# IO_Expander.net
KiCad netlist of a schematic drawn in Altium Designer
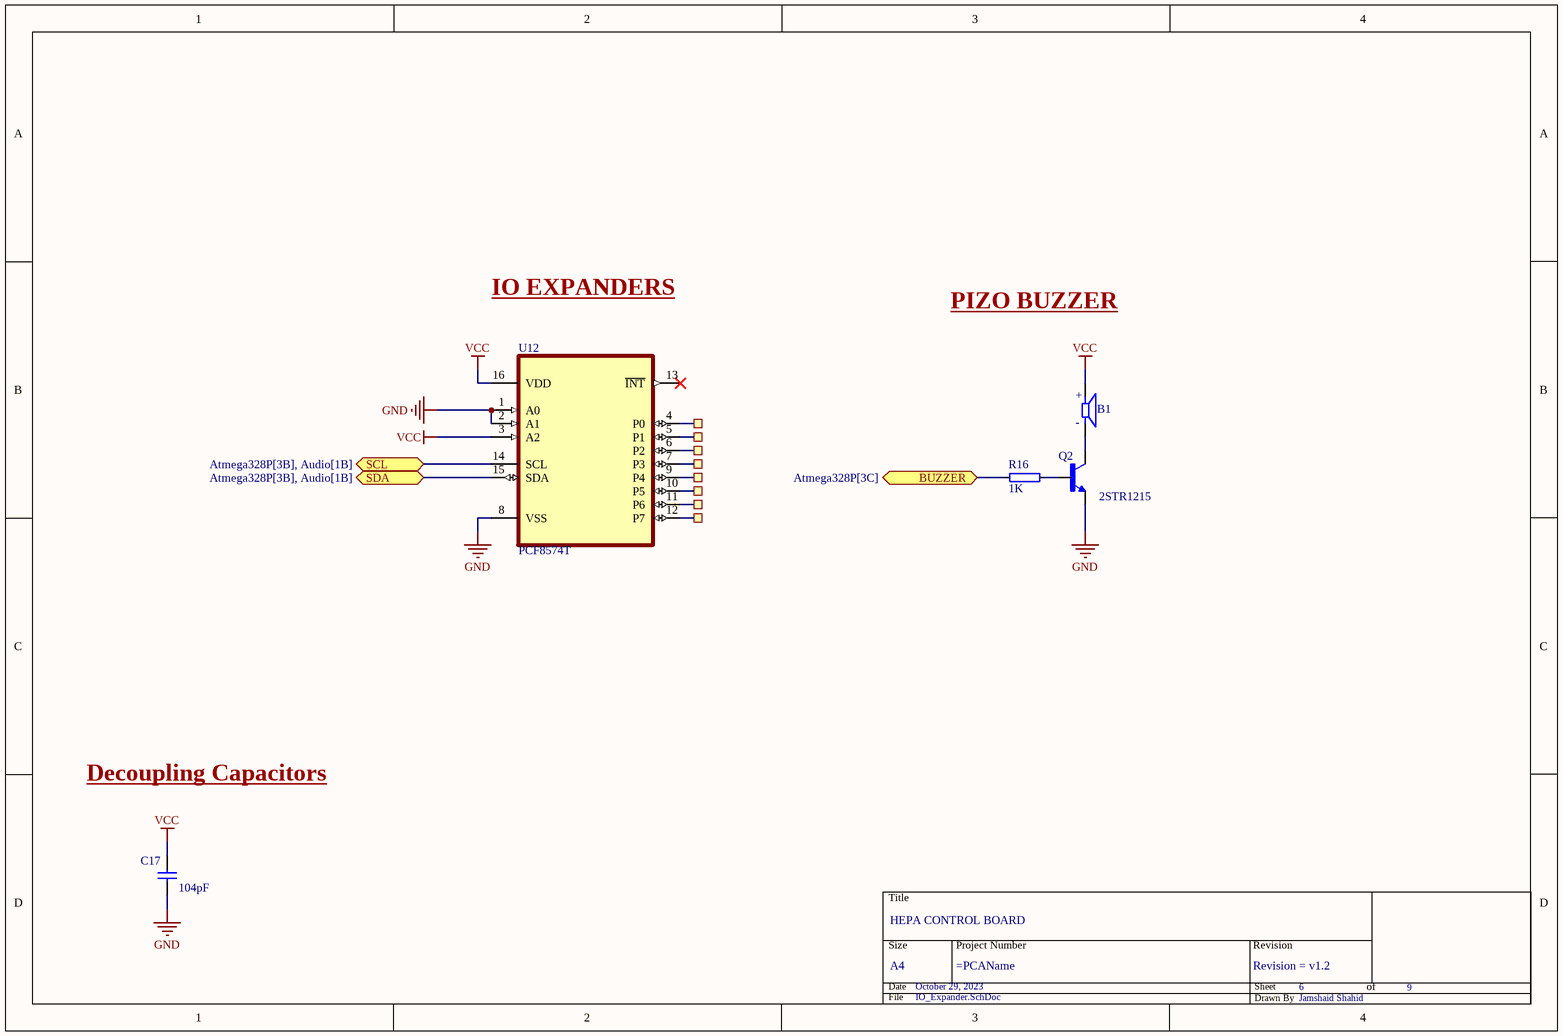
[diagram p0: IO_Expander.SchDoc]

(export (version "E")
  (design (tool "Eeschema 10.0.6"))
  (components
    (comp (ref "B1")
      (value "CST-951AP")
      (footprint "CUI_CST-951AP")
      (description "9 mm, 5 V, 85 dB, Through Hole, Magnetic Audio Transducer B")
      (fields (field (name "PUBLISHER") "Metal Circuits"))
      (libsource (lib "HEPA_LIB") (part "CST-951AP"))
    )
    (comp (ref "C17")
      (value "104pF")
      (footprint "CAPC2012X140N")
      (fields (field (name "PART NUMBER") "CAP_0805") (field (name "PUBLISHER") "Metal Circuits"))
      (libsource (lib "HEPA_LIB") (part "CAP_0805"))
    )
    (comp (ref "Q2")
      (value "2STR1215")
      (footprint "SOT95P280X125-3N")
      (description "Bipolar (BJT) Transistor NPN 15 V 1.5 A - 500 mW Surface Mount SOT-23-3")
      (fields (field (name "MANUFACTURER") "ST") (field (name "PUBLISHER") "Metal Circuits"))
      (libsource (lib "HEPA_LIB") (part "2STR1215"))
    )
    (comp (ref "R16")
      (value "1K")
      (footprint "RESC2012X65N")
      (description "RES SMD 1% 1/10W 0805")
      (fields (field (name "PART NUMBER") "RES_0805") (field (name "PUBLISHER") "Metal Circuits"))
      (libsource (lib "HEPA_LIB") (part "RES_0805"))
    )
    (comp (ref "TP3")
      (value "TP")
      (footprint "TESTPAD-TH")
      (description "Testpoint, through hole")
      (fields (field (name "PART NUMBER") "Testpoint TH") (field (name "PUBLISHER") "Nordic Semiconductor"))
      (libsource (lib "HEPA_LIB") (part "TESTPAD_TH"))
    )
    (comp (ref "TP4")
      (value "TP")
      (footprint "TESTPAD-TH")
      (description "Testpoint, through hole")
      (fields (field (name "PART NUMBER") "Testpoint TH") (field (name "PUBLISHER") "Nordic Semiconductor"))
      (libsource (lib "HEPA_LIB") (part "TESTPAD_TH"))
    )
    (comp (ref "TP5")
      (value "TP")
      (footprint "TESTPAD-TH")
      (description "Testpoint, through hole")
      (fields (field (name "PART NUMBER") "Testpoint TH") (field (name "PUBLISHER") "Nordic Semiconductor"))
      (libsource (lib "HEPA_LIB") (part "TESTPAD_TH"))
    )
    (comp (ref "TP6")
      (value "TP")
      (footprint "TESTPAD-TH")
      (description "Testpoint, through hole")
      (fields (field (name "PART NUMBER") "Testpoint TH") (field (name "PUBLISHER") "Nordic Semiconductor"))
      (libsource (lib "HEPA_LIB") (part "TESTPAD_TH"))
    )
    (comp (ref "TP7")
      (value "TP")
      (footprint "TESTPAD-TH")
      (description "Testpoint, through hole")
      (fields (field (name "PART NUMBER") "Testpoint TH") (field (name "PUBLISHER") "Nordic Semiconductor"))
      (libsource (lib "HEPA_LIB") (part "TESTPAD_TH"))
    )
    (comp (ref "TP8")
      (value "TP")
      (footprint "TESTPAD-TH")
      (description "Testpoint, through hole")
      (fields (field (name "PART NUMBER") "Testpoint TH") (field (name "PUBLISHER") "Nordic Semiconductor"))
      (libsource (lib "HEPA_LIB") (part "TESTPAD_TH"))
    )
    (comp (ref "TP9")
      (value "TP")
      (footprint "TESTPAD-TH")
      (description "Testpoint, through hole")
      (fields (field (name "PART NUMBER") "Testpoint TH") (field (name "PUBLISHER") "Nordic Semiconductor"))
      (libsource (lib "HEPA_LIB") (part "TESTPAD_TH"))
    )
    (comp (ref "TP10")
      (value "TP")
      (footprint "TESTPAD-TH")
      (description "Testpoint, through hole")
      (fields (field (name "PART NUMBER") "Testpoint TH") (field (name "PUBLISHER") "Nordic Semiconductor"))
      (libsource (lib "HEPA_LIB") (part "TESTPAD_TH"))
    )
    (comp (ref "U12")
      (value "PCF8574T")
      (footprint "SOIC127P1032X265-16N")
      (description "IC XPNDR 100KHZ I2C 16SO")
      (fields
        (field (name "PART NUMBER") "PCF8574T/3,518")
        (field (name "MANUFACTURER") "NXP")
        (field (name "PUBLISHER") "Metal Circuits")
      )
      (libsource (lib "HEPA_LIB") (part "PCF8574T/3,518"))
    )
  )
  (nets
    (net (code "1") (name "/BUZZER") (class "Default")
      (node (ref "R16") (pin "2") (pinfunction "2_2") (pintype "passive"))
    )
    (net (code "2") (name "/SCL") (class "Default")
      (node (ref "U12") (pin "14") (pinfunction "SCL_14") (pintype "passive"))
    )
    (net (code "3") (name "/SDA") (class "Default")
      (node (ref "U12") (pin "15") (pinfunction "SDA_15") (pintype "bidirectional"))
    )
    (net (code "4") (name "GND") (class "Default")
      (node (ref "C17") (pin "1") (pinfunction "1_1") (pintype "passive"))
      (node (ref "Q2") (pin "2") (pinfunction "E_2") (pintype "passive"))
      (node (ref "U12") (pin "1") (pinfunction "A0_1") (pintype "input"))
      (node (ref "U12") (pin "2") (pinfunction "A1_2") (pintype "input"))
      (node (ref "U12") (pin "8") (pinfunction "VSS_8") (pintype "passive"))
    )
    (net (code "5") (name "Net-(Q2-B)") (class "Default")
      (node (ref "Q2") (pin "1") (pinfunction "B_1") (pintype "passive"))
      (node (ref "R16") (pin "1") (pinfunction "1_1") (pintype "passive"))
    )
    (net (code "6") (name "Net-(Q2-C)") (class "Default")
      (node (ref "B1") (pin "M") (pinfunction "M_M") (pintype "passive"))
      (node (ref "Q2") (pin "3") (pinfunction "C_3") (pintype "passive"))
    )
    (net (code "7") (name "Net-(U12-P0)") (class "Default")
      (node (ref "TP3") (pin "1") (pinfunction "1_1") (pintype "passive"))
      (node (ref "U12") (pin "4") (pinfunction "P0_4") (pintype "bidirectional"))
    )
    (net (code "8") (name "Net-(U12-P1)") (class "Default")
      (node (ref "TP4") (pin "1") (pinfunction "1_1") (pintype "passive"))
      (node (ref "U12") (pin "5") (pinfunction "P1_5") (pintype "bidirectional"))
    )
    (net (code "9") (name "Net-(U12-P2)") (class "Default")
      (node (ref "TP5") (pin "1") (pinfunction "1_1") (pintype "passive"))
      (node (ref "U12") (pin "6") (pinfunction "P2_6") (pintype "bidirectional"))
    )
    (net (code "10") (name "Net-(U12-P3)") (class "Default")
      (node (ref "TP6") (pin "1") (pinfunction "1_1") (pintype "passive"))
      (node (ref "U12") (pin "7") (pinfunction "P3_7") (pintype "bidirectional"))
    )
    (net (code "11") (name "Net-(U12-P4)") (class "Default")
      (node (ref "TP7") (pin "1") (pinfunction "1_1") (pintype "passive"))
      (node (ref "U12") (pin "9") (pinfunction "P4_9") (pintype "bidirectional"))
    )
    (net (code "12") (name "Net-(U12-P5)") (class "Default")
      (node (ref "TP8") (pin "1") (pinfunction "1_1") (pintype "passive"))
      (node (ref "U12") (pin "10") (pinfunction "P5_10") (pintype "bidirectional"))
    )
    (net (code "13") (name "Net-(U12-P6)") (class "Default")
      (node (ref "TP9") (pin "1") (pinfunction "1_1") (pintype "passive"))
      (node (ref "U12") (pin "11") (pinfunction "P6_11") (pintype "bidirectional"))
    )
    (net (code "14") (name "Net-(U12-P7)") (class "Default")
      (node (ref "TP10") (pin "1") (pinfunction "1_1") (pintype "passive"))
      (node (ref "U12") (pin "12") (pinfunction "P7_12") (pintype "bidirectional"))
    )
    (net (code "15") (name "VCC") (class "Default")
      (node (ref "B1") (pin "P") (pinfunction "P_P") (pintype "passive"))
      (node (ref "C17") (pin "2") (pinfunction "2_2") (pintype "passive"))
      (node (ref "U12") (pin "16") (pinfunction "VDD_16") (pintype "power_in"))
      (node (ref "U12") (pin "3") (pinfunction "A2_3") (pintype "input"))
    )
    (net (code "16") (name "unconnected-(U12-~{INT}-Pad13)") (class "Default")
      (node (ref "U12") (pin "13") (pinfunction "~{INT}_13") (pintype "output+no_connect"))
    )
  )
)
